# AT89S52S_L298.net
KiCad netlist of a schematic drawn in Altium Designer
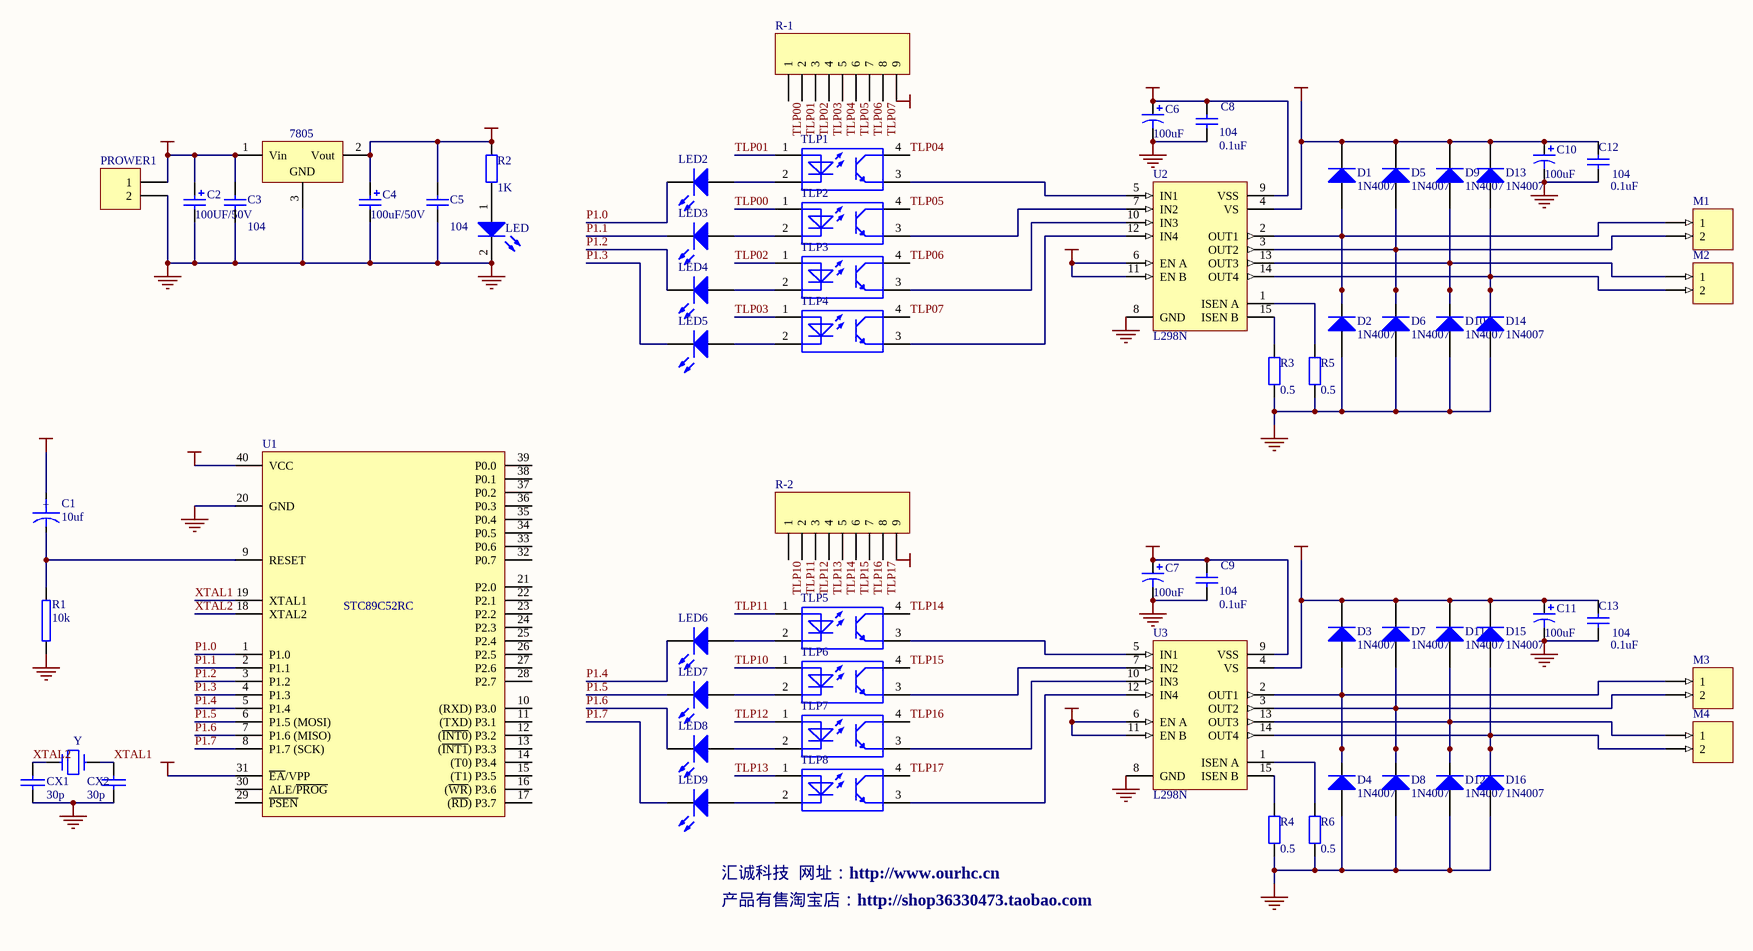
[diagram p0: AT89S52S双L298驱动控制器.SCHDOC]

(export (version "E")
  (design (tool "Eeschema 10.0.6"))
  (components
    (comp (ref "7805")
      (value "SDWYG")
      (footprint "WYG")
      (description "三端稳压器")
      (fields (field (name "PUBLISHER") "Altium Limited"))
      (libsource (lib "zxcourhc") (part "SDWYG"))
    )
    (comp (ref "C1")
      (value "10uf")
      (footprint "C-DJ-4")
      (description "Capacitor")
      (libsource (lib "*") (part "CAPACITOR POL"))
    )
    (comp (ref "C2")
      (value "100UF/50V")
      (footprint "C-DJ-6")
      (description "电解电容")
      (fields (field (name "Comment") "DJDR") (field (name "PUBLISHER") "Altium Limited"))
      (libsource (lib "zxcourhc") (part "DJDR"))
    )
    (comp (ref "C3")
      (value "104")
      (footprint "CPDR")
      (description "瓷片电容")
      (fields (field (name "Comment") "CPDR") (field (name "PUBLISHER") "Altium Limited"))
      (libsource (lib "zxcourhc") (part "CPDR"))
    )
    (comp (ref "C4")
      (value "100uF/50V")
      (footprint "C-DJ-6")
      (description "电解电容")
      (fields (field (name "Comment") "DJDR") (field (name "PUBLISHER") "Altium Limited"))
      (libsource (lib "zxcourhc") (part "DJDR"))
    )
    (comp (ref "C5")
      (value "104")
      (footprint "CPDR")
      (description "瓷片电容")
      (fields (field (name "Comment") "CPDR") (field (name "PUBLISHER") "Altium Limited"))
      (libsource (lib "zxcourhc") (part "CPDR"))
    )
    (comp (ref "C6")
      (value "100uF")
      (footprint "C-DJ-6")
      (description "Polarized Capacitor (Surface Mount)")
      (fields (field (name "PUBLISHER") "Altium Limited"))
      (libsource (lib "Miscellaneous Devices") (part "Cap Pol3"))
    )
    (comp (ref "C7")
      (value "100uF")
      (footprint "C-DJ-6")
      (description "Polarized Capacitor (Surface Mount)")
      (fields (field (name "PUBLISHER") "Altium Limited"))
      (libsource (lib "Miscellaneous Devices") (part "Cap Pol3"))
    )
    (comp (ref "C8")
      (value "104")
      (footprint "CPDR")
      (description "Capacitor")
      (fields (field (name "ALTIUM_VALUE") "0.1uF") (field (name "PUBLISHER") "Altium Limited"))
      (libsource (lib "Miscellaneous Devices") (part "Cap"))
    )
    (comp (ref "C9")
      (value "104")
      (footprint "CPDR")
      (description "Capacitor")
      (fields (field (name "ALTIUM_VALUE") "0.1uF") (field (name "PUBLISHER") "Altium Limited"))
      (libsource (lib "Miscellaneous Devices") (part "Cap"))
    )
    (comp (ref "C10")
      (value "100uF")
      (footprint "C-DJ-6")
      (description "Polarized Capacitor (Surface Mount)")
      (fields (field (name "PUBLISHER") "Altium Limited"))
      (libsource (lib "Miscellaneous Devices") (part "Cap Pol3"))
    )
    (comp (ref "C11")
      (value "100uF")
      (footprint "C-DJ-6")
      (description "Polarized Capacitor (Surface Mount)")
      (fields (field (name "PUBLISHER") "Altium Limited"))
      (libsource (lib "Miscellaneous Devices") (part "Cap Pol3"))
    )
    (comp (ref "C12")
      (value "104")
      (footprint "CPDR")
      (description "Capacitor")
      (fields (field (name "ALTIUM_VALUE") "0.1uF") (field (name "PUBLISHER") "Altium Limited"))
      (libsource (lib "Miscellaneous Devices") (part "Cap"))
    )
    (comp (ref "C13")
      (value "104")
      (footprint "CPDR")
      (description "Capacitor")
      (fields (field (name "ALTIUM_VALUE") "0.1uF") (field (name "PUBLISHER") "Altium Limited"))
      (libsource (lib "Miscellaneous Devices") (part "Cap"))
    )
    (comp (ref "CX1")
      (value "30p")
      (footprint "HDR1X2")
      (description "Capacitor")
      (libsource (lib "*") (part "CAP"))
    )
    (comp (ref "CX2")
      (value "30p")
      (footprint "HDR1X2")
      (description "Capacitor")
      (libsource (lib "*") (part "CAP"))
    )
    (comp (ref "D1")
      (value "1N4007")
      (footprint "DIO7.8-4.6x2")
      (description "1 Amp General Purpose Rectifier")
      (fields (field (name "PUBLISHER") "Altium Limited"))
      (libsource (lib "Miscellaneous Devices") (part "Diode 1N4007"))
    )
    (comp (ref "D2")
      (value "1N4007")
      (footprint "DIO7.8-4.6x2")
      (description "1 Amp General Purpose Rectifier")
      (fields (field (name "PUBLISHER") "Altium Limited"))
      (libsource (lib "Miscellaneous Devices") (part "Diode 1N4007"))
    )
    (comp (ref "D3")
      (value "1N4007")
      (footprint "DIO7.8-4.6x2")
      (description "1 Amp General Purpose Rectifier")
      (fields (field (name "PUBLISHER") "Altium Limited"))
      (libsource (lib "Miscellaneous Devices") (part "Diode 1N4007"))
    )
    (comp (ref "D4")
      (value "1N4007")
      (footprint "DIO7.8-4.6x2")
      (description "1 Amp General Purpose Rectifier")
      (fields (field (name "PUBLISHER") "Altium Limited"))
      (libsource (lib "Miscellaneous Devices") (part "Diode 1N4007"))
    )
    (comp (ref "D5")
      (value "1N4007")
      (footprint "DIO7.8-4.6x2")
      (description "1 Amp General Purpose Rectifier")
      (fields (field (name "PUBLISHER") "Altium Limited"))
      (libsource (lib "Miscellaneous Devices") (part "Diode 1N4007"))
    )
    (comp (ref "D6")
      (value "1N4007")
      (footprint "DIO7.8-4.6x2")
      (description "1 Amp General Purpose Rectifier")
      (fields (field (name "PUBLISHER") "Altium Limited"))
      (libsource (lib "Miscellaneous Devices") (part "Diode 1N4007"))
    )
    (comp (ref "D7")
      (value "1N4007")
      (footprint "DIO7.8-4.6x2")
      (description "1 Amp General Purpose Rectifier")
      (fields (field (name "PUBLISHER") "Altium Limited"))
      (libsource (lib "Miscellaneous Devices") (part "Diode 1N4007"))
    )
    (comp (ref "D8")
      (value "1N4007")
      (footprint "DIO7.8-4.6x2")
      (description "1 Amp General Purpose Rectifier")
      (fields (field (name "PUBLISHER") "Altium Limited"))
      (libsource (lib "Miscellaneous Devices") (part "Diode 1N4007"))
    )
    (comp (ref "D9")
      (value "1N4007")
      (footprint "DIO7.8-4.6x2")
      (description "1 Amp General Purpose Rectifier")
      (fields (field (name "PUBLISHER") "Altium Limited"))
      (libsource (lib "Miscellaneous Devices") (part "Diode 1N4007"))
    )
    (comp (ref "D10")
      (value "1N4007")
      (footprint "DIO7.8-4.6x2")
      (description "1 Amp General Purpose Rectifier")
      (fields (field (name "PUBLISHER") "Altium Limited"))
      (libsource (lib "Miscellaneous Devices") (part "Diode 1N4007"))
    )
    (comp (ref "D11")
      (value "1N4007")
      (footprint "DIO7.8-4.6x2")
      (description "1 Amp General Purpose Rectifier")
      (fields (field (name "PUBLISHER") "Altium Limited"))
      (libsource (lib "Miscellaneous Devices") (part "Diode 1N4007"))
    )
    (comp (ref "D12")
      (value "1N4007")
      (footprint "DIO7.8-4.6x2")
      (description "1 Amp General Purpose Rectifier")
      (fields (field (name "PUBLISHER") "Altium Limited"))
      (libsource (lib "Miscellaneous Devices") (part "Diode 1N4007"))
    )
    (comp (ref "D13")
      (value "1N4007")
      (footprint "DIO7.8-4.6x2")
      (description "1 Amp General Purpose Rectifier")
      (fields (field (name "PUBLISHER") "Altium Limited"))
      (libsource (lib "Miscellaneous Devices") (part "Diode 1N4007"))
    )
    (comp (ref "D14")
      (value "1N4007")
      (footprint "DIO7.8-4.6x2")
      (description "1 Amp General Purpose Rectifier")
      (fields (field (name "PUBLISHER") "Altium Limited"))
      (libsource (lib "Miscellaneous Devices") (part "Diode 1N4007"))
    )
    (comp (ref "D15")
      (value "1N4007")
      (footprint "DIO7.8-4.6x2")
      (description "1 Amp General Purpose Rectifier")
      (fields (field (name "PUBLISHER") "Altium Limited"))
      (libsource (lib "Miscellaneous Devices") (part "Diode 1N4007"))
    )
    (comp (ref "D16")
      (value "1N4007")
      (footprint "DIO7.8-4.6x2")
      (description "1 Amp General Purpose Rectifier")
      (fields (field (name "PUBLISHER") "Altium Limited"))
      (libsource (lib "Miscellaneous Devices") (part "Diode 1N4007"))
    )
    (comp (ref "LED1")
      (value "LED")
      (footprint "LED_D")
      (description "发光二极管")
      (fields (field (name "PUBLISHER") "Altium Limited"))
      (libsource (lib "zxcourhc") (part "LED"))
    )
    (comp (ref "LED2")
      (value "~")
      (footprint "LED_D")
      (description "Typical BLUE SiC LED")
      (fields (field (name "PUBLISHER") "Altium Limited"))
      (libsource (lib "Miscellaneous Devices") (part "LED3"))
    )
    (comp (ref "LED3")
      (value "~")
      (footprint "LED_D")
      (description "Typical BLUE SiC LED")
      (fields (field (name "PUBLISHER") "Altium Limited"))
      (libsource (lib "Miscellaneous Devices") (part "LED3"))
    )
    (comp (ref "LED4")
      (value "~")
      (footprint "LED_D")
      (description "Typical BLUE SiC LED")
      (fields (field (name "PUBLISHER") "Altium Limited"))
      (libsource (lib "Miscellaneous Devices") (part "LED3"))
    )
    (comp (ref "LED5")
      (value "~")
      (footprint "LED_D")
      (description "Typical BLUE SiC LED")
      (fields (field (name "PUBLISHER") "Altium Limited"))
      (libsource (lib "Miscellaneous Devices") (part "LED3"))
    )
    (comp (ref "LED6")
      (value "~")
      (footprint "LED_D")
      (description "Typical BLUE SiC LED")
      (fields (field (name "PUBLISHER") "Altium Limited"))
      (libsource (lib "Miscellaneous Devices") (part "LED3"))
    )
    (comp (ref "LED7")
      (value "~")
      (footprint "LED_D")
      (description "Typical BLUE SiC LED")
      (fields (field (name "PUBLISHER") "Altium Limited"))
      (libsource (lib "Miscellaneous Devices") (part "LED3"))
    )
    (comp (ref "LED8")
      (value "~")
      (footprint "LED_D")
      (description "Typical BLUE SiC LED")
      (fields (field (name "PUBLISHER") "Altium Limited"))
      (libsource (lib "Miscellaneous Devices") (part "LED3"))
    )
    (comp (ref "LED9")
      (value "~")
      (footprint "LED_D")
      (description "Typical BLUE SiC LED")
      (fields (field (name "PUBLISHER") "Altium Limited"))
      (libsource (lib "Miscellaneous Devices") (part "LED3"))
    )
    (comp (ref "M1")
      (value "~")
      (footprint "DYDZ")
      (description "Header, 2-Pin")
      (fields (field (name "PUBLISHER") "Altium Limited"))
      (libsource (lib "Miscellaneous Connectors") (part "MHDR1X2"))
    )
    (comp (ref "M2")
      (value "~")
      (footprint "DYDZ")
      (description "Header, 2-Pin")
      (fields (field (name "PUBLISHER") "Altium Limited"))
      (libsource (lib "Miscellaneous Connectors") (part "MHDR1X2"))
    )
    (comp (ref "M3")
      (value "~")
      (footprint "DYDZ")
      (description "Header, 2-Pin")
      (fields (field (name "PUBLISHER") "Altium Limited"))
      (libsource (lib "Miscellaneous Connectors") (part "MHDR1X2"))
    )
    (comp (ref "M4")
      (value "~")
      (footprint "DYDZ")
      (description "Header, 2-Pin")
      (fields (field (name "PUBLISHER") "Altium Limited"))
      (libsource (lib "Miscellaneous Connectors") (part "MHDR1X2"))
    )
    (comp (ref "PROWER1")
      (value "PZ_2")
      (footprint "zxcourhc:DYDZ")
      (description "排针——2")
      (fields (field (name "PUBLISHER") "Altium Limited"))
      (libsource (lib "zxcourhc") (part "PZ_2"))
    )
    (comp (ref "R-1")
      (value "~")
      (footprint "HDR1X9")
      (description "Header, 9-Pin")
      (fields (field (name "PUBLISHER") "Altium Limited"))
      (libsource (lib "Miscellaneous Connectors") (part "Header 9"))
    )
    (comp (ref "R-2")
      (value "~")
      (footprint "HDR1X9")
      (description "Header, 9-Pin")
      (fields (field (name "PUBLISHER") "Altium Limited"))
      (libsource (lib "Miscellaneous Connectors") (part "Header 9"))
    )
    (comp (ref "R1") (value "10k") (footprint "RSE") (libsource (lib "*") (part "RES2")))
    (comp (ref "R2")
      (value "1K")
      (footprint "RSE")
      (description "电阻")
      (fields (field (name "Comment") "Res") (field (name "PUBLISHER") "Altium Limited"))
      (libsource (lib "zxcourhc") (part "Res"))
    )
    (comp (ref "R3")
      (value "0.5")
      (footprint "ZCDZL")
      (description "Resistor")
      (fields (field (name "Comment") "Res2") (field (name "PUBLISHER") "Altium Limited"))
      (libsource (lib "Miscellaneous Devices") (part "Res2"))
    )
    (comp (ref "R4")
      (value "0.5")
      (footprint "ZCDZL")
      (description "Resistor")
      (fields (field (name "Comment") "Res2") (field (name "PUBLISHER") "Altium Limited"))
      (libsource (lib "Miscellaneous Devices") (part "Res2"))
    )
    (comp (ref "R5")
      (value "0.5")
      (footprint "ZCDZL")
      (description "Resistor")
      (fields (field (name "Comment") "Res2") (field (name "PUBLISHER") "Altium Limited"))
      (libsource (lib "Miscellaneous Devices") (part "Res2"))
    )
    (comp (ref "R6")
      (value "0.5")
      (footprint "ZCDZL")
      (description "Resistor")
      (fields (field (name "Comment") "Res2") (field (name "PUBLISHER") "Altium Limited"))
      (libsource (lib "Miscellaneous Devices") (part "Res2"))
    )
    (comp (ref "TLP1") (value "~") (footprint "DIP-4") (libsource (lib "MyInt_Lib") (part "TLP521-1")))
    (comp (ref "TLP2") (value "~") (footprint "DIP-4") (libsource (lib "MyInt_Lib") (part "TLP521-1")))
    (comp (ref "TLP3") (value "~") (footprint "DIP-4") (libsource (lib "MyInt_Lib") (part "TLP521-1")))
    (comp (ref "TLP4") (value "~") (footprint "DIP-4") (libsource (lib "MyInt_Lib") (part "TLP521-1")))
    (comp (ref "TLP5") (value "~") (footprint "DIP-4") (libsource (lib "MyInt_Lib") (part "TLP521-1")))
    (comp (ref "TLP6") (value "~") (footprint "DIP-4") (libsource (lib "MyInt_Lib") (part "TLP521-1")))
    (comp (ref "TLP7") (value "~") (footprint "DIP-4") (libsource (lib "MyInt_Lib") (part "TLP521-1")))
    (comp (ref "TLP8") (value "~") (footprint "DIP-4") (libsource (lib "MyInt_Lib") (part "TLP521-1")))
    (comp (ref "U1")
      (value "STC89C52RC")
      (footprint "DIP-40")
      (description "8 位微处理器/40引脚")
      (fields (field (name "发布者") "磊元工作室"))
      (libsource (lib "MCU") (part "AT89S52-P"))
    )
    (comp (ref "U2")
      (value "L298N")
      (footprint "L298N")
      (description "Dual Full Bridge Driver")
      (fields (field (name "PUBLISHER") "Altium Limited"))
      (libsource (lib "ST Interface DC Motor Controller") (part "L298N"))
    )
    (comp (ref "U3")
      (value "L298N")
      (footprint "L298N")
      (description "Dual Full Bridge Driver")
      (fields (field (name "PUBLISHER") "Altium Limited"))
      (libsource (lib "ST Interface DC Motor Controller") (part "L298N"))
    )
    (comp (ref "Y1")
      (value "Y")
      (footprint "JZ_ZC")
      (description "Crystal")
      (libsource (lib "*") (part "CRYSTAL"))
    )
  )
  (nets
    (net (code "1") (name "+5V") (class "Default")
      (node (ref "7805") (pin "2") (pinfunction "Vout_2") (pintype "passive"))
      (node (ref "C1") (pin "1") (pinfunction "1_1") (pintype "passive"))
      (node (ref "C4") (pin "1") (pinfunction "1_1") (pintype "passive"))
      (node (ref "C5") (pin "2") (pinfunction "2_2") (pintype "passive"))
      (node (ref "C6") (pin "1") (pinfunction "1_1") (pintype "passive"))
      (node (ref "C7") (pin "1") (pinfunction "1_1") (pintype "passive"))
      (node (ref "C8") (pin "2") (pinfunction "2_2") (pintype "passive"))
      (node (ref "C9") (pin "2") (pinfunction "2_2") (pintype "passive"))
      (node (ref "R-1") (pin "9") (pinfunction "9_9") (pintype "passive"))
      (node (ref "R-2") (pin "9") (pinfunction "9_9") (pintype "passive"))
      (node (ref "R2") (pin "2") (pinfunction "2_2") (pintype "passive"))
      (node (ref "U1") (pin "31") (pinfunction "~{EA}/VPP_31") (pintype "passive"))
      (node (ref "U1") (pin "40") (pinfunction "VCC_40") (pintype "power_in"))
      (node (ref "U2") (pin "11") (pinfunction "EN_B_11") (pintype "input"))
      (node (ref "U2") (pin "6") (pinfunction "EN_A_6") (pintype "input"))
      (node (ref "U2") (pin "9") (pinfunction "VSS_9") (pintype "power_in"))
      (node (ref "U3") (pin "11") (pinfunction "EN_B_11") (pintype "input"))
      (node (ref "U3") (pin "6") (pinfunction "EN_A_6") (pintype "input"))
      (node (ref "U3") (pin "9") (pinfunction "VSS_9") (pintype "power_in"))
    )
    (net (code "2") (name "+12V") (class "Default")
      (node (ref "7805") (pin "1") (pinfunction "Vin_1") (pintype "passive"))
      (node (ref "C10") (pin "1") (pinfunction "1_1") (pintype "passive"))
      (node (ref "C11") (pin "1") (pinfunction "1_1") (pintype "passive"))
      (node (ref "C12") (pin "2") (pinfunction "2_2") (pintype "passive"))
      (node (ref "C13") (pin "2") (pinfunction "2_2") (pintype "passive"))
      (node (ref "C2") (pin "1") (pinfunction "1_1") (pintype "passive"))
      (node (ref "C3") (pin "2") (pinfunction "2_2") (pintype "passive"))
      (node (ref "D1") (pin "2") (pinfunction "K_2") (pintype "passive"))
      (node (ref "D11") (pin "2") (pinfunction "K_2") (pintype "passive"))
      (node (ref "D13") (pin "2") (pinfunction "K_2") (pintype "passive"))
      (node (ref "D15") (pin "2") (pinfunction "K_2") (pintype "passive"))
      (node (ref "D3") (pin "2") (pinfunction "K_2") (pintype "passive"))
      (node (ref "D5") (pin "2") (pinfunction "K_2") (pintype "passive"))
      (node (ref "D7") (pin "2") (pinfunction "K_2") (pintype "passive"))
      (node (ref "D9") (pin "2") (pinfunction "K_2") (pintype "passive"))
      (node (ref "PROWER1") (pin "1") (pinfunction "1_1") (pintype "passive"))
      (node (ref "U2") (pin "4") (pinfunction "VS_4") (pintype "power_in"))
      (node (ref "U3") (pin "4") (pinfunction "VS_4") (pintype "power_in"))
    )
    (net (code "3") (name "/P1.0") (class "Default")
      (node (ref "LED2") (pin "2") (pinfunction "K_2") (pintype "passive"))
      (node (ref "U1") (pin "1") (pinfunction "P1.0_1") (pintype "passive"))
    )
    (net (code "4") (name "/P1.1") (class "Default")
      (node (ref "LED3") (pin "2") (pinfunction "K_2") (pintype "passive"))
      (node (ref "U1") (pin "2") (pinfunction "P1.1_2") (pintype "passive"))
    )
    (net (code "5") (name "/P1.2") (class "Default")
      (node (ref "LED4") (pin "2") (pinfunction "K_2") (pintype "passive"))
      (node (ref "U1") (pin "3") (pinfunction "P1.2_3") (pintype "passive"))
    )
    (net (code "6") (name "/P1.3") (class "Default")
      (node (ref "LED5") (pin "2") (pinfunction "K_2") (pintype "passive"))
      (node (ref "U1") (pin "4") (pinfunction "P1.3_4") (pintype "passive"))
    )
    (net (code "7") (name "/P1.4") (class "Default")
      (node (ref "LED6") (pin "2") (pinfunction "K_2") (pintype "passive"))
      (node (ref "U1") (pin "5") (pinfunction "P1.4_5") (pintype "passive"))
    )
    (net (code "8") (name "/P1.5") (class "Default")
      (node (ref "LED7") (pin "2") (pinfunction "K_2") (pintype "passive"))
      (node (ref "U1") (pin "6") (pinfunction "P1.5_(MOSI)_6") (pintype "passive"))
    )
    (net (code "9") (name "/P1.6") (class "Default")
      (node (ref "LED8") (pin "2") (pinfunction "K_2") (pintype "passive"))
      (node (ref "U1") (pin "7") (pinfunction "P1.6_(MISO)_7") (pintype "passive"))
    )
    (net (code "10") (name "/P1.7") (class "Default")
      (node (ref "LED9") (pin "2") (pinfunction "K_2") (pintype "passive"))
      (node (ref "U1") (pin "8") (pinfunction "P1.7_(SCK)_8") (pintype "passive"))
    )
    (net (code "11") (name "/TLP00") (class "Default")
      (node (ref "R-1") (pin "1") (pinfunction "1_1") (pintype "passive"))
      (node (ref "TLP2") (pin "1") (pinfunction "1_1") (pintype "passive"))
    )
    (net (code "12") (name "/TLP01") (class "Default")
      (node (ref "R-1") (pin "2") (pinfunction "2_2") (pintype "passive"))
      (node (ref "TLP1") (pin "1") (pinfunction "1_1") (pintype "passive"))
    )
    (net (code "13") (name "/TLP02") (class "Default")
      (node (ref "R-1") (pin "3") (pinfunction "3_3") (pintype "passive"))
      (node (ref "TLP3") (pin "1") (pinfunction "1_1") (pintype "passive"))
    )
    (net (code "14") (name "/TLP03") (class "Default")
      (node (ref "R-1") (pin "4") (pinfunction "4_4") (pintype "passive"))
      (node (ref "TLP4") (pin "1") (pinfunction "1_1") (pintype "passive"))
    )
    (net (code "15") (name "/TLP04") (class "Default")
      (node (ref "R-1") (pin "5") (pinfunction "5_5") (pintype "passive"))
      (node (ref "TLP1") (pin "4") (pinfunction "4_4") (pintype "passive"))
    )
    (net (code "16") (name "/TLP05") (class "Default")
      (node (ref "R-1") (pin "6") (pinfunction "6_6") (pintype "passive"))
      (node (ref "TLP2") (pin "4") (pinfunction "4_4") (pintype "passive"))
    )
    (net (code "17") (name "/TLP06") (class "Default")
      (node (ref "R-1") (pin "7") (pinfunction "7_7") (pintype "passive"))
      (node (ref "TLP3") (pin "4") (pinfunction "4_4") (pintype "passive"))
    )
    (net (code "18") (name "/TLP07") (class "Default")
      (node (ref "R-1") (pin "8") (pinfunction "8_8") (pintype "passive"))
      (node (ref "TLP4") (pin "4") (pinfunction "4_4") (pintype "passive"))
    )
    (net (code "19") (name "/TLP10") (class "Default")
      (node (ref "R-2") (pin "1") (pinfunction "1_1") (pintype "passive"))
      (node (ref "TLP6") (pin "1") (pinfunction "1_1") (pintype "passive"))
    )
    (net (code "20") (name "/TLP11") (class "Default")
      (node (ref "R-2") (pin "2") (pinfunction "2_2") (pintype "passive"))
      (node (ref "TLP5") (pin "1") (pinfunction "1_1") (pintype "passive"))
    )
    (net (code "21") (name "/TLP12") (class "Default")
      (node (ref "R-2") (pin "3") (pinfunction "3_3") (pintype "passive"))
      (node (ref "TLP7") (pin "1") (pinfunction "1_1") (pintype "passive"))
    )
    (net (code "22") (name "/TLP13") (class "Default")
      (node (ref "R-2") (pin "4") (pinfunction "4_4") (pintype "passive"))
      (node (ref "TLP8") (pin "1") (pinfunction "1_1") (pintype "passive"))
    )
    (net (code "23") (name "/TLP14") (class "Default")
      (node (ref "R-2") (pin "5") (pinfunction "5_5") (pintype "passive"))
      (node (ref "TLP5") (pin "4") (pinfunction "4_4") (pintype "passive"))
    )
    (net (code "24") (name "/TLP15") (class "Default")
      (node (ref "R-2") (pin "6") (pinfunction "6_6") (pintype "passive"))
      (node (ref "TLP6") (pin "4") (pinfunction "4_4") (pintype "passive"))
    )
    (net (code "25") (name "/TLP16") (class "Default")
      (node (ref "R-2") (pin "7") (pinfunction "7_7") (pintype "passive"))
      (node (ref "TLP7") (pin "4") (pinfunction "4_4") (pintype "passive"))
    )
    (net (code "26") (name "/TLP17") (class "Default")
      (node (ref "R-2") (pin "8") (pinfunction "8_8") (pintype "passive"))
      (node (ref "TLP8") (pin "4") (pinfunction "4_4") (pintype "passive"))
    )
    (net (code "27") (name "/XTAL1") (class "Default")
      (node (ref "CX2") (pin "1") (pinfunction "1_1") (pintype "passive"))
      (node (ref "U1") (pin "19") (pinfunction "XTAL1_19") (pintype "passive"))
      (node (ref "Y1") (pin "1") (pinfunction "1_1") (pintype "passive"))
    )
    (net (code "28") (name "/XTAL2") (class "Default")
      (node (ref "CX1") (pin "1") (pinfunction "1_1") (pintype "passive"))
      (node (ref "U1") (pin "18") (pinfunction "XTAL2_18") (pintype "passive"))
      (node (ref "Y1") (pin "2") (pinfunction "2_2") (pintype "passive"))
    )
    (net (code "29") (name "GND") (class "Default")
      (node (ref "7805") (pin "3") (pinfunction "GND_3") (pintype "passive"))
      (node (ref "C10") (pin "2") (pinfunction "2_2") (pintype "passive"))
      (node (ref "C11") (pin "2") (pinfunction "2_2") (pintype "passive"))
      (node (ref "C12") (pin "1") (pinfunction "1_1") (pintype "passive"))
      (node (ref "C13") (pin "1") (pinfunction "1_1") (pintype "passive"))
      (node (ref "C2") (pin "2") (pinfunction "2_2") (pintype "passive"))
      (node (ref "C3") (pin "1") (pinfunction "1_1") (pintype "passive"))
      (node (ref "C4") (pin "2") (pinfunction "2_2") (pintype "passive"))
      (node (ref "C5") (pin "1") (pinfunction "1_1") (pintype "passive"))
      (node (ref "C6") (pin "2") (pinfunction "2_2") (pintype "passive"))
      (node (ref "C7") (pin "2") (pinfunction "2_2") (pintype "passive"))
      (node (ref "C8") (pin "1") (pinfunction "1_1") (pintype "passive"))
      (node (ref "C9") (pin "1") (pinfunction "1_1") (pintype "passive"))
      (node (ref "CX1") (pin "2") (pinfunction "2_2") (pintype "passive"))
      (node (ref "CX2") (pin "2") (pinfunction "2_2") (pintype "passive"))
      (node (ref "D10") (pin "1") (pinfunction "A_1") (pintype "passive"))
      (node (ref "D12") (pin "1") (pinfunction "A_1") (pintype "passive"))
      (node (ref "D14") (pin "1") (pinfunction "A_1") (pintype "passive"))
      (node (ref "D16") (pin "1") (pinfunction "A_1") (pintype "passive"))
      (node (ref "D2") (pin "1") (pinfunction "A_1") (pintype "passive"))
      (node (ref "D4") (pin "1") (pinfunction "A_1") (pintype "passive"))
      (node (ref "D6") (pin "1") (pinfunction "A_1") (pintype "passive"))
      (node (ref "D8") (pin "1") (pinfunction "A_1") (pintype "passive"))
      (node (ref "LED1") (pin "2") (pinfunction "K_2") (pintype "passive"))
      (node (ref "PROWER1") (pin "2") (pinfunction "2_2") (pintype "passive"))
      (node (ref "R1") (pin "1") (pinfunction "1_1") (pintype "passive"))
      (node (ref "R3") (pin "1") (pinfunction "1_1") (pintype "passive"))
      (node (ref "R4") (pin "1") (pinfunction "1_1") (pintype "passive"))
      (node (ref "R5") (pin "1") (pinfunction "1_1") (pintype "passive"))
      (node (ref "R6") (pin "1") (pinfunction "1_1") (pintype "passive"))
      (node (ref "U1") (pin "20") (pinfunction "GND_20") (pintype "power_in"))
      (node (ref "U2") (pin "8") (pinfunction "GND_8") (pintype "power_in"))
      (node (ref "U3") (pin "8") (pinfunction "GND_8") (pintype "power_in"))
    )
    (net (code "30") (name "Net-(D1-A)") (class "Default")
      (node (ref "D1") (pin "1") (pinfunction "A_1") (pintype "passive"))
      (node (ref "D2") (pin "2") (pinfunction "K_2") (pintype "passive"))
      (node (ref "M1") (pin "1") (pinfunction "1_1") (pintype "input"))
      (node (ref "U2") (pin "2") (pinfunction "OUT1_2") (pintype "output"))
    )
    (net (code "31") (name "Net-(D3-A)") (class "Default")
      (node (ref "D3") (pin "1") (pinfunction "A_1") (pintype "passive"))
      (node (ref "D4") (pin "2") (pinfunction "K_2") (pintype "passive"))
      (node (ref "M3") (pin "1") (pinfunction "1_1") (pintype "input"))
      (node (ref "U3") (pin "2") (pinfunction "OUT1_2") (pintype "output"))
    )
    (net (code "32") (name "Net-(D5-A)") (class "Default")
      (node (ref "D5") (pin "1") (pinfunction "A_1") (pintype "passive"))
      (node (ref "D6") (pin "2") (pinfunction "K_2") (pintype "passive"))
      (node (ref "M1") (pin "2") (pinfunction "2_2") (pintype "input"))
      (node (ref "U2") (pin "3") (pinfunction "OUT2_3") (pintype "output"))
    )
    (net (code "33") (name "Net-(D7-A)") (class "Default")
      (node (ref "D7") (pin "1") (pinfunction "A_1") (pintype "passive"))
      (node (ref "D8") (pin "2") (pinfunction "K_2") (pintype "passive"))
      (node (ref "M3") (pin "2") (pinfunction "2_2") (pintype "input"))
      (node (ref "U3") (pin "3") (pinfunction "OUT2_3") (pintype "output"))
    )
    (net (code "34") (name "Net-(D10-K)") (class "Default")
      (node (ref "D10") (pin "2") (pinfunction "K_2") (pintype "passive"))
      (node (ref "D9") (pin "1") (pinfunction "A_1") (pintype "passive"))
      (node (ref "M2") (pin "1") (pinfunction "1_1") (pintype "input"))
      (node (ref "U2") (pin "13") (pinfunction "OUT3_13") (pintype "output"))
    )
    (net (code "35") (name "Net-(D11-A)") (class "Default")
      (node (ref "D11") (pin "1") (pinfunction "A_1") (pintype "passive"))
      (node (ref "D12") (pin "2") (pinfunction "K_2") (pintype "passive"))
      (node (ref "M4") (pin "1") (pinfunction "1_1") (pintype "input"))
      (node (ref "U3") (pin "13") (pinfunction "OUT3_13") (pintype "output"))
    )
    (net (code "36") (name "Net-(D13-A)") (class "Default")
      (node (ref "D13") (pin "1") (pinfunction "A_1") (pintype "passive"))
      (node (ref "D14") (pin "2") (pinfunction "K_2") (pintype "passive"))
      (node (ref "M2") (pin "2") (pinfunction "2_2") (pintype "input"))
      (node (ref "U2") (pin "14") (pinfunction "OUT4_14") (pintype "output"))
    )
    (net (code "37") (name "Net-(D15-A)") (class "Default")
      (node (ref "D15") (pin "1") (pinfunction "A_1") (pintype "passive"))
      (node (ref "D16") (pin "2") (pinfunction "K_2") (pintype "passive"))
      (node (ref "M4") (pin "2") (pinfunction "2_2") (pintype "input"))
      (node (ref "U3") (pin "14") (pinfunction "OUT4_14") (pintype "output"))
    )
    (net (code "38") (name "Net-(LED1-A)") (class "Default")
      (node (ref "LED1") (pin "1") (pinfunction "A_1") (pintype "passive"))
      (node (ref "R2") (pin "1") (pinfunction "1_1") (pintype "passive"))
    )
    (net (code "39") (name "Net-(LED2-A)") (class "Default")
      (node (ref "LED2") (pin "1") (pinfunction "A_1") (pintype "passive"))
      (node (ref "TLP1") (pin "2") (pinfunction "2_2") (pintype "passive"))
    )
    (net (code "40") (name "Net-(LED3-A)") (class "Default")
      (node (ref "LED3") (pin "1") (pinfunction "A_1") (pintype "passive"))
      (node (ref "TLP2") (pin "2") (pinfunction "2_2") (pintype "passive"))
    )
    (net (code "41") (name "Net-(LED4-A)") (class "Default")
      (node (ref "LED4") (pin "1") (pinfunction "A_1") (pintype "passive"))
      (node (ref "TLP3") (pin "2") (pinfunction "2_2") (pintype "passive"))
    )
    (net (code "42") (name "Net-(LED5-A)") (class "Default")
      (node (ref "LED5") (pin "1") (pinfunction "A_1") (pintype "passive"))
      (node (ref "TLP4") (pin "2") (pinfunction "2_2") (pintype "passive"))
    )
    (net (code "43") (name "Net-(LED6-A)") (class "Default")
      (node (ref "LED6") (pin "1") (pinfunction "A_1") (pintype "passive"))
      (node (ref "TLP5") (pin "2") (pinfunction "2_2") (pintype "passive"))
    )
    (net (code "44") (name "Net-(LED7-A)") (class "Default")
      (node (ref "LED7") (pin "1") (pinfunction "A_1") (pintype "passive"))
      (node (ref "TLP6") (pin "2") (pinfunction "2_2") (pintype "passive"))
    )
    (net (code "45") (name "Net-(LED8-A)") (class "Default")
      (node (ref "LED8") (pin "1") (pinfunction "A_1") (pintype "passive"))
      (node (ref "TLP7") (pin "2") (pinfunction "2_2") (pintype "passive"))
    )
    (net (code "46") (name "Net-(LED9-A)") (class "Default")
      (node (ref "LED9") (pin "1") (pinfunction "A_1") (pintype "passive"))
      (node (ref "TLP8") (pin "2") (pinfunction "2_2") (pintype "passive"))
    )
    (net (code "47") (name "Net-(U1-RESET)") (class "Default")
      (node (ref "C1") (pin "2") (pinfunction "2_2") (pintype "passive"))
      (node (ref "R1") (pin "2") (pinfunction "2_2") (pintype "passive"))
      (node (ref "U1") (pin "9") (pinfunction "RESET_9") (pintype "passive"))
    )
    (net (code "48") (name "Net-(U2-IN1)") (class "Default")
      (node (ref "TLP1") (pin "3") (pinfunction "3_3") (pintype "passive"))
      (node (ref "U2") (pin "5") (pinfunction "IN1_5") (pintype "input"))
    )
    (net (code "49") (name "Net-(U2-IN2)") (class "Default")
      (node (ref "TLP2") (pin "3") (pinfunction "3_3") (pintype "passive"))
      (node (ref "U2") (pin "7") (pinfunction "IN2_7") (pintype "input"))
    )
    (net (code "50") (name "Net-(U2-IN3)") (class "Default")
      (node (ref "TLP3") (pin "3") (pinfunction "3_3") (pintype "passive"))
      (node (ref "U2") (pin "10") (pinfunction "IN3_10") (pintype "input"))
    )
    (net (code "51") (name "Net-(U2-IN4)") (class "Default")
      (node (ref "TLP4") (pin "3") (pinfunction "3_3") (pintype "passive"))
      (node (ref "U2") (pin "12") (pinfunction "IN4_12") (pintype "input"))
    )
    (net (code "52") (name "Net-(U2-ISEN_A)") (class "Default")
      (node (ref "R5") (pin "2") (pinfunction "2_2") (pintype "passive"))
      (node (ref "U2") (pin "1") (pinfunction "ISEN_A_1") (pintype "passive"))
    )
    (net (code "53") (name "Net-(U2-ISEN_B)") (class "Default")
      (node (ref "R3") (pin "2") (pinfunction "2_2") (pintype "passive"))
      (node (ref "U2") (pin "15") (pinfunction "ISEN_B_15") (pintype "passive"))
    )
    (net (code "54") (name "Net-(U3-IN1)") (class "Default")
      (node (ref "TLP5") (pin "3") (pinfunction "3_3") (pintype "passive"))
      (node (ref "U3") (pin "5") (pinfunction "IN1_5") (pintype "input"))
    )
    (net (code "55") (name "Net-(U3-IN2)") (class "Default")
      (node (ref "TLP6") (pin "3") (pinfunction "3_3") (pintype "passive"))
      (node (ref "U3") (pin "7") (pinfunction "IN2_7") (pintype "input"))
    )
    (net (code "56") (name "Net-(U3-IN3)") (class "Default")
      (node (ref "TLP7") (pin "3") (pinfunction "3_3") (pintype "passive"))
      (node (ref "U3") (pin "10") (pinfunction "IN3_10") (pintype "input"))
    )
    (net (code "57") (name "Net-(U3-IN4)") (class "Default")
      (node (ref "TLP8") (pin "3") (pinfunction "3_3") (pintype "passive"))
      (node (ref "U3") (pin "12") (pinfunction "IN4_12") (pintype "input"))
    )
    (net (code "58") (name "Net-(U3-ISEN_A)") (class "Default")
      (node (ref "R6") (pin "2") (pinfunction "2_2") (pintype "passive"))
      (node (ref "U3") (pin "1") (pinfunction "ISEN_A_1") (pintype "passive"))
    )
    (net (code "59") (name "Net-(U3-ISEN_B)") (class "Default")
      (node (ref "R4") (pin "2") (pinfunction "2_2") (pintype "passive"))
      (node (ref "U3") (pin "15") (pinfunction "ISEN_B_15") (pintype "passive"))
    )
    (net (code "60") (name "unconnected-(U1-(RXD)_P3.0-Pad10)") (class "Default")
      (node (ref "U1") (pin "10") (pinfunction "(RXD)_P3.0_10") (pintype "passive"))
    )
    (net (code "61") (name "unconnected-(U1-(T0)_P3.4-Pad14)") (class "Default")
      (node (ref "U1") (pin "14") (pinfunction "(T0)_P3.4_14") (pintype "passive"))
    )
    (net (code "62") (name "unconnected-(U1-(T1)_P3.5-Pad15)") (class "Default")
      (node (ref "U1") (pin "15") (pinfunction "(T1)_P3.5_15") (pintype "passive"))
    )
    (net (code "63") (name "unconnected-(U1-(TXD)_P3.1-Pad11)") (class "Default")
      (node (ref "U1") (pin "11") (pinfunction "(TXD)_P3.1_11") (pintype "passive"))
    )
    (net (code "64") (name "unconnected-(U1-(~{INT0})_P3.2-Pad12)") (class "Default")
      (node (ref "U1") (pin "12") (pinfunction "(~{INT0})_P3.2_12") (pintype "passive"))
    )
    (net (code "65") (name "unconnected-(U1-(~{INT1})_P3.3-Pad13)") (class "Default")
      (node (ref "U1") (pin "13") (pinfunction "(~{INT1})_P3.3_13") (pintype "passive"))
    )
    (net (code "66") (name "unconnected-(U1-(~{RD})_P3.7-Pad17)") (class "Default")
      (node (ref "U1") (pin "17") (pinfunction "(~{RD})_P3.7_17") (pintype "passive"))
    )
    (net (code "67") (name "unconnected-(U1-(~{WR})_P3.6-Pad16)") (class "Default")
      (node (ref "U1") (pin "16") (pinfunction "(~{WR})_P3.6_16") (pintype "passive"))
    )
    (net (code "68") (name "unconnected-(U1-ALE{slash}~{PROG}-Pad30)") (class "Default")
      (node (ref "U1") (pin "30") (pinfunction "ALE/~{PROG}_30") (pintype "passive"))
    )
    (net (code "69") (name "unconnected-(U1-P0.0-Pad39)") (class "Default")
      (node (ref "U1") (pin "39") (pinfunction "P0.0_39") (pintype "passive"))
    )
    (net (code "70") (name "unconnected-(U1-P0.1-Pad38)") (class "Default")
      (node (ref "U1") (pin "38") (pinfunction "P0.1_38") (pintype "passive"))
    )
    (net (code "71") (name "unconnected-(U1-P0.2-Pad37)") (class "Default")
      (node (ref "U1") (pin "37") (pinfunction "P0.2_37") (pintype "passive"))
    )
    (net (code "72") (name "unconnected-(U1-P0.3-Pad36)") (class "Default")
      (node (ref "U1") (pin "36") (pinfunction "P0.3_36") (pintype "passive"))
    )
    (net (code "73") (name "unconnected-(U1-P0.4-Pad35)") (class "Default")
      (node (ref "U1") (pin "35") (pinfunction "P0.4_35") (pintype "passive"))
    )
    (net (code "74") (name "unconnected-(U1-P0.5-Pad34)") (class "Default")
      (node (ref "U1") (pin "34") (pinfunction "P0.5_34") (pintype "passive"))
    )
    (net (code "75") (name "unconnected-(U1-P0.6-Pad33)") (class "Default")
      (node (ref "U1") (pin "33") (pinfunction "P0.6_33") (pintype "passive"))
    )
    (net (code "76") (name "unconnected-(U1-P0.7-Pad32)") (class "Default")
      (node (ref "U1") (pin "32") (pinfunction "P0.7_32") (pintype "passive"))
    )
    (net (code "77") (name "unconnected-(U1-P2.0-Pad21)") (class "Default")
      (node (ref "U1") (pin "21") (pinfunction "P2.0_21") (pintype "passive"))
    )
    (net (code "78") (name "unconnected-(U1-P2.1-Pad22)") (class "Default")
      (node (ref "U1") (pin "22") (pinfunction "P2.1_22") (pintype "passive"))
    )
    (net (code "79") (name "unconnected-(U1-P2.2-Pad23)") (class "Default")
      (node (ref "U1") (pin "23") (pinfunction "P2.2_23") (pintype "passive"))
    )
    (net (code "80") (name "unconnected-(U1-P2.3-Pad24)") (class "Default")
      (node (ref "U1") (pin "24") (pinfunction "P2.3_24") (pintype "passive"))
    )
    (net (code "81") (name "unconnected-(U1-P2.4-Pad25)") (class "Default")
      (node (ref "U1") (pin "25") (pinfunction "P2.4_25") (pintype "passive"))
    )
    (net (code "82") (name "unconnected-(U1-P2.5-Pad26)") (class "Default")
      (node (ref "U1") (pin "26") (pinfunction "P2.5_26") (pintype "passive"))
    )
    (net (code "83") (name "unconnected-(U1-P2.6-Pad27)") (class "Default")
      (node (ref "U1") (pin "27") (pinfunction "P2.6_27") (pintype "passive"))
    )
    (net (code "84") (name "unconnected-(U1-P2.7-Pad28)") (class "Default")
      (node (ref "U1") (pin "28") (pinfunction "P2.7_28") (pintype "passive"))
    )
    (net (code "85") (name "unconnected-(U1-~{PSEN}-Pad29)") (class "Default")
      (node (ref "U1") (pin "29") (pinfunction "~{PSEN}_29") (pintype "passive"))
    )
  )
)
